# MovimientoALIM.net
KiCad netlist of a schematic drawn in EAGLE
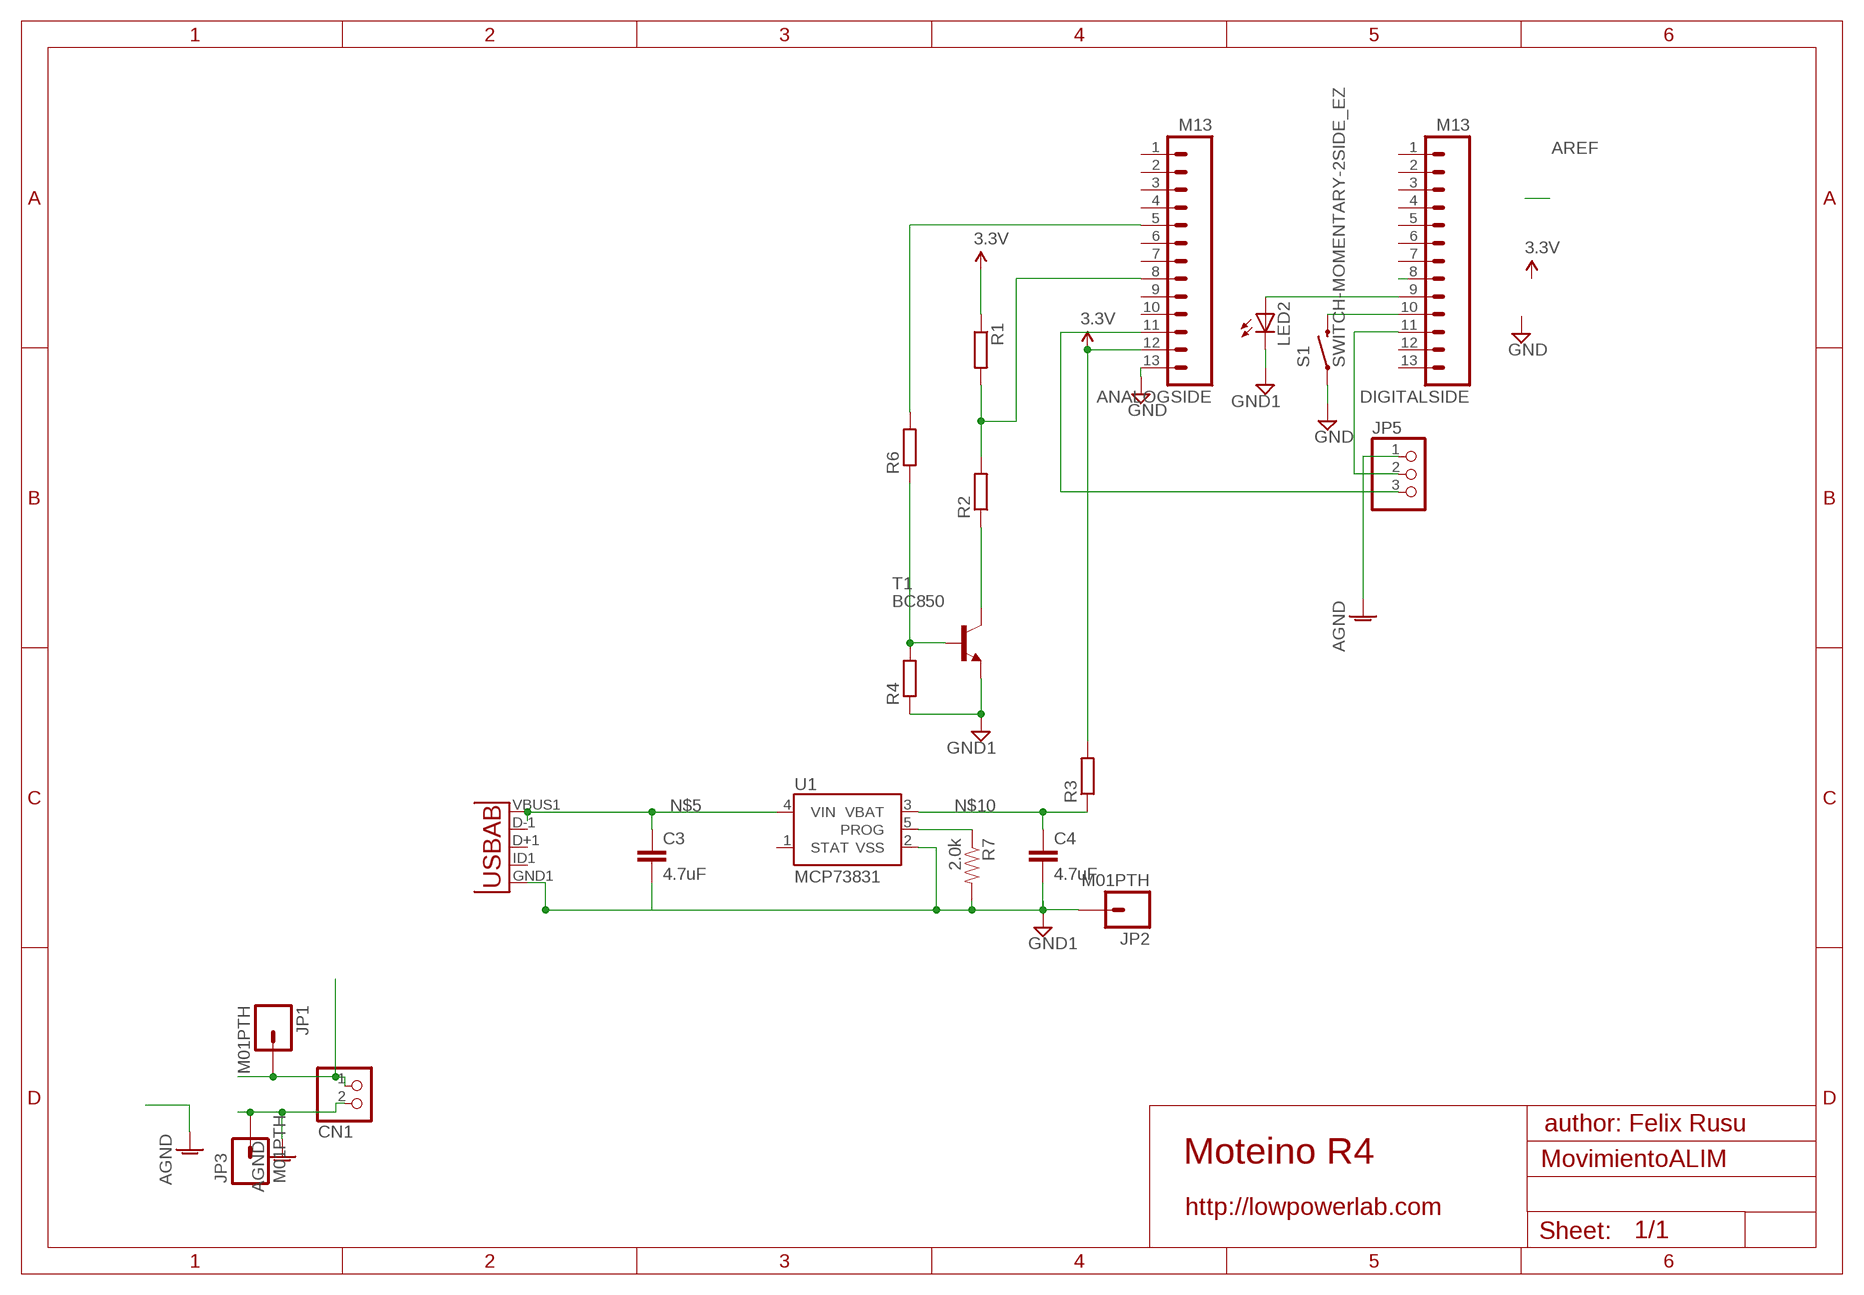
[diagram p0: schematic, sheet 1]

(export (version "E")
  (design (tool "Eeschema 10.0.6"))
  (components
    (comp (ref "ANALOGSIDE")
      (value "M13")
      (footprint "eagle-import:1X13")
      (libsource (lib "eagle-import") (part "M13"))
    )
    (comp (ref "C3")
      (value "4.7uF")
      (footprint "eagle-import:0603-CAP")
      (libsource (lib "eagle-import") (part "4.7UF-6.3V-10%(0603)0603"))
    )
    (comp (ref "C4")
      (value "4.7uF")
      (footprint "eagle-import:0603-CAP")
      (libsource (lib "eagle-import") (part "4.7UF-6.3V-10%(0603)0603"))
    )
    (comp (ref "CN1")
      (value "JST_2PIN-SMT")
      (footprint "eagle-import:JST-PH-2-SMT")
      (libsource (lib "eagle-import") (part "JST_2PIN-SMT"))
    )
    (comp (ref "DIGITALSIDE")
      (value "M13")
      (footprint "eagle-import:1X13")
      (libsource (lib "eagle-import") (part "M13"))
    )
    (comp (ref "JP1")
      (value "M01PTH")
      (footprint "eagle-import:1X01")
      (libsource (lib "eagle-import") (part "M01PTH"))
    )
    (comp (ref "JP2")
      (value "M01PTH")
      (footprint "eagle-import:1X01")
      (libsource (lib "eagle-import") (part "M01PTH"))
    )
    (comp (ref "JP3")
      (value "M01PTH")
      (footprint "eagle-import:1X01")
      (libsource (lib "eagle-import") (part "M01PTH"))
    )
    (comp (ref "JP5")
      (value "PINHD-1X3")
      (footprint "eagle-import:1X03")
      (libsource (lib "eagle-import") (part "PINHD-1X3"))
    )
    (comp (ref "JP9")
      (value "Micro USB")
      (footprint "eagle-import:USB-AB-MICRO-SMD_V03")
      (libsource (lib "eagle-import") (part "USB-ABCONN-11794"))
    )
    (comp (ref "LED2")
      (value "LED3MM")
      (footprint "eagle-import:LED3MM")
      (libsource (lib "eagle-import") (part "LED3MM"))
    )
    (comp (ref "R1")
      (value "R-EU_0204/7")
      (footprint "eagle-import:0204_7")
      (libsource (lib "eagle-import") (part "R-EU_0204/7"))
    )
    (comp (ref "R2")
      (value "R-EU_0204/7")
      (footprint "eagle-import:0204_7")
      (libsource (lib "eagle-import") (part "R-EU_0204/7"))
    )
    (comp (ref "R3")
      (value "R-EU_M1206")
      (footprint "eagle-import:M1206")
      (libsource (lib "eagle-import") (part "R-EU_M1206"))
    )
    (comp (ref "R4")
      (value "R-EU_M1206")
      (footprint "eagle-import:M1206")
      (libsource (lib "eagle-import") (part "R-EU_M1206"))
    )
    (comp (ref "R6")
      (value "R-EU_M1206")
      (footprint "eagle-import:M1206")
      (libsource (lib "eagle-import") (part "R-EU_M1206"))
    )
    (comp (ref "R7")
      (value "2.0k")
      (footprint "eagle-import:0603-RES")
      (libsource (lib "eagle-import") (part "2.0KOHM1/10W5%(0603)"))
    )
    (comp (ref "S1")
      (value "SWITCH-MOMENTARY-2SIDE_EZ")
      (footprint "eagle-import:TACTILE-PTH-SIDEEZ")
      (libsource (lib "eagle-import") (part "SWITCH-MOMENTARY-2SIDE_EZ"))
    )
    (comp (ref "T1")
      (value "BC850")
      (footprint "eagle-import:SOT23")
      (libsource (lib "eagle-import") (part "BC850"))
    )
    (comp (ref "U1")
      (value "MCP73831")
      (footprint "eagle-import:SOT23-5")
      (libsource (lib "eagle-import") (part "MCP73831"))
    )
  )
  (nets
    (net (code "2") (name "/N$5") (class "Default")
      (node (ref "C3") (pin "1") (pinfunction "1_1") (pintype "passive"))
      (node (ref "JP9") (pin "VBUS1") (pinfunction "VBUS_VBUS1") (pintype "bidirectional"))
      (node (ref "U1") (pin "4") (pinfunction "VIN_4") (pintype "power_in"))
    )
    (net (code "3") (name "/N$10") (class "Default")
      (node (ref "C4") (pin "1") (pinfunction "1_1") (pintype "passive"))
      (node (ref "R3") (pin "1") (pinfunction "1_1") (pintype "passive"))
      (node (ref "U1") (pin "3") (pinfunction "VBAT_3") (pintype "power_in"))
    )
    (net (code "4") (name "3.3V") (class "Default")
      (node (ref "ANALOGSIDE") (pin "12") (pinfunction "12_12") (pintype "passive"))
      (node (ref "R1") (pin "1") (pinfunction "1_1") (pintype "passive"))
      (node (ref "R3") (pin "2") (pinfunction "2_2") (pintype "passive"))
    )
    (net (code "5") (name "AGND") (class "Default")
      (node (ref "CN1") (pin "2") (pinfunction "1_2") (pintype "passive"))
      (node (ref "JP3") (pin "1") (pinfunction "1_1") (pintype "passive"))
      (node (ref "JP5") (pin "1") (pinfunction "1_1") (pintype "passive"))
    )
    (net (code "6") (name "GND") (class "Default")
      (node (ref "ANALOGSIDE") (pin "13") (pinfunction "13_13") (pintype "passive"))
      (node (ref "S1") (pin "1") (pinfunction "1_1") (pintype "passive"))
    )
    (net (code "7") (name "GND1") (class "Default")
      (node (ref "C3") (pin "2") (pinfunction "2_2") (pintype "passive"))
      (node (ref "C4") (pin "2") (pinfunction "2_2") (pintype "passive"))
      (node (ref "JP2") (pin "1") (pinfunction "1_1") (pintype "passive"))
      (node (ref "JP9") (pin "GND1") (pinfunction "GND_GND1") (pintype "bidirectional"))
      (node (ref "LED2") (pin "K") (pinfunction "C_K") (pintype "passive"))
      (node (ref "R4") (pin "1") (pinfunction "1_1") (pintype "passive"))
      (node (ref "R7") (pin "2") (pinfunction "2_2") (pintype "passive"))
      (node (ref "T1") (pin "2") (pinfunction "E_2") (pintype "passive"))
      (node (ref "U1") (pin "2") (pinfunction "VSS_2") (pintype "power_in"))
    )
    (net (code "8") (name "Net-(ANALOGSIDE-Pad5)") (class "Default")
      (node (ref "ANALOGSIDE") (pin "5") (pinfunction "5_5") (pintype "passive"))
      (node (ref "R6") (pin "2") (pinfunction "2_2") (pintype "passive"))
    )
    (net (code "9") (name "Net-(ANALOGSIDE-Pad8)") (class "Default")
      (node (ref "ANALOGSIDE") (pin "8") (pinfunction "8_8") (pintype "passive"))
      (node (ref "R1") (pin "2") (pinfunction "2_2") (pintype "passive"))
      (node (ref "R2") (pin "2") (pinfunction "2_2") (pintype "passive"))
    )
    (net (code "10") (name "Net-(ANALOGSIDE-Pad11)") (class "Default")
      (node (ref "ANALOGSIDE") (pin "11") (pinfunction "11_11") (pintype "passive"))
      (node (ref "JP5") (pin "3") (pinfunction "3_3") (pintype "passive"))
    )
    (net (code "11") (name "Net-(CN1-2)") (class "Default")
      (node (ref "CN1") (pin "1") (pinfunction "2_1") (pintype "passive"))
      (node (ref "JP1") (pin "1") (pinfunction "1_1") (pintype "passive"))
    )
    (net (code "12") (name "Net-(DIGITALSIDE-Pad9)") (class "Default")
      (node (ref "DIGITALSIDE") (pin "9") (pinfunction "9_9") (pintype "passive"))
      (node (ref "LED2") (pin "A") (pinfunction "A_A") (pintype "passive"))
    )
    (net (code "13") (name "Net-(DIGITALSIDE-Pad10)") (class "Default")
      (node (ref "DIGITALSIDE") (pin "10") (pinfunction "10_10") (pintype "passive"))
      (node (ref "S1") (pin "2") (pinfunction "2_2") (pintype "passive"))
    )
    (net (code "14") (name "Net-(DIGITALSIDE-Pad11)") (class "Default")
      (node (ref "DIGITALSIDE") (pin "11") (pinfunction "11_11") (pintype "passive"))
      (node (ref "JP5") (pin "2") (pinfunction "2_2") (pintype "passive"))
    )
    (net (code "15") (name "Net-(T1-B)") (class "Default")
      (node (ref "R4") (pin "2") (pinfunction "2_2") (pintype "passive"))
      (node (ref "R6") (pin "1") (pinfunction "1_1") (pintype "passive"))
      (node (ref "T1") (pin "1") (pinfunction "B_1") (pintype "passive"))
    )
    (net (code "16") (name "Net-(T1-C)") (class "Default")
      (node (ref "R2") (pin "1") (pinfunction "1_1") (pintype "passive"))
      (node (ref "T1") (pin "3") (pinfunction "C_3") (pintype "passive"))
    )
    (net (code "17") (name "Net-(U1-PROG)") (class "Default")
      (node (ref "R7") (pin "1") (pinfunction "1_1") (pintype "passive"))
      (node (ref "U1") (pin "5") (pinfunction "PROG_5") (pintype "input"))
    )
    (net (code "18") (name "unconnected-(ANALOGSIDE-Pad1)") (class "Default")
      (node (ref "ANALOGSIDE") (pin "1") (pinfunction "1_1") (pintype "passive"))
    )
    (net (code "19") (name "unconnected-(ANALOGSIDE-Pad2)") (class "Default")
      (node (ref "ANALOGSIDE") (pin "2") (pinfunction "2_2") (pintype "passive"))
    )
    (net (code "20") (name "unconnected-(ANALOGSIDE-Pad3)") (class "Default")
      (node (ref "ANALOGSIDE") (pin "3") (pinfunction "3_3") (pintype "passive"))
    )
    (net (code "21") (name "unconnected-(ANALOGSIDE-Pad4)") (class "Default")
      (node (ref "ANALOGSIDE") (pin "4") (pinfunction "4_4") (pintype "passive"))
    )
    (net (code "22") (name "unconnected-(ANALOGSIDE-Pad6)") (class "Default")
      (node (ref "ANALOGSIDE") (pin "6") (pinfunction "6_6") (pintype "passive"))
    )
    (net (code "23") (name "unconnected-(ANALOGSIDE-Pad7)") (class "Default")
      (node (ref "ANALOGSIDE") (pin "7") (pinfunction "7_7") (pintype "passive"))
    )
    (net (code "24") (name "unconnected-(ANALOGSIDE-Pad9)") (class "Default")
      (node (ref "ANALOGSIDE") (pin "9") (pinfunction "9_9") (pintype "passive"))
    )
    (net (code "25") (name "unconnected-(ANALOGSIDE-Pad10)") (class "Default")
      (node (ref "ANALOGSIDE") (pin "10") (pinfunction "10_10") (pintype "passive"))
    )
    (net (code "26") (name "unconnected-(DIGITALSIDE-Pad1)") (class "Default")
      (node (ref "DIGITALSIDE") (pin "1") (pinfunction "1_1") (pintype "passive"))
    )
    (net (code "27") (name "unconnected-(DIGITALSIDE-Pad2)") (class "Default")
      (node (ref "DIGITALSIDE") (pin "2") (pinfunction "2_2") (pintype "passive"))
    )
    (net (code "28") (name "unconnected-(DIGITALSIDE-Pad3)") (class "Default")
      (node (ref "DIGITALSIDE") (pin "3") (pinfunction "3_3") (pintype "passive"))
    )
    (net (code "29") (name "unconnected-(DIGITALSIDE-Pad4)") (class "Default")
      (node (ref "DIGITALSIDE") (pin "4") (pinfunction "4_4") (pintype "passive"))
    )
    (net (code "30") (name "unconnected-(DIGITALSIDE-Pad5)") (class "Default")
      (node (ref "DIGITALSIDE") (pin "5") (pinfunction "5_5") (pintype "passive"))
    )
    (net (code "31") (name "unconnected-(DIGITALSIDE-Pad6)") (class "Default")
      (node (ref "DIGITALSIDE") (pin "6") (pinfunction "6_6") (pintype "passive"))
    )
    (net (code "32") (name "unconnected-(DIGITALSIDE-Pad7)") (class "Default")
      (node (ref "DIGITALSIDE") (pin "7") (pinfunction "7_7") (pintype "passive"))
    )
    (net (code "33") (name "unconnected-(DIGITALSIDE-Pad8)") (class "Default")
      (node (ref "DIGITALSIDE") (pin "8") (pinfunction "8_8") (pintype "passive"))
    )
    (net (code "34") (name "unconnected-(DIGITALSIDE-Pad12)") (class "Default")
      (node (ref "DIGITALSIDE") (pin "12") (pinfunction "12_12") (pintype "passive"))
    )
    (net (code "35") (name "unconnected-(DIGITALSIDE-Pad13)") (class "Default")
      (node (ref "DIGITALSIDE") (pin "13") (pinfunction "13_13") (pintype "passive"))
    )
    (net (code "36") (name "unconnected-(JP9-D+-PadD+1)") (class "Default")
      (node (ref "JP9") (pin "D+1") (pinfunction "D+_D+1") (pintype "bidirectional"))
    )
    (net (code "37") (name "unconnected-(JP9-D--PadD-1)") (class "Default")
      (node (ref "JP9") (pin "D-1") (pinfunction "D-_D-1") (pintype "bidirectional"))
    )
    (net (code "38") (name "unconnected-(JP9-USBID-PadID1)") (class "Default")
      (node (ref "JP9") (pin "ID1") (pinfunction "USBID_ID1") (pintype "bidirectional"))
    )
    (net (code "39") (name "unconnected-(U1-STAT-Pad1)") (class "Default")
      (node (ref "U1") (pin "1") (pinfunction "STAT_1") (pintype "output"))
    )
  )
)
